# thesolderstation_v0_1.net
KiCad netlist of a schematic drawn in EAGLE
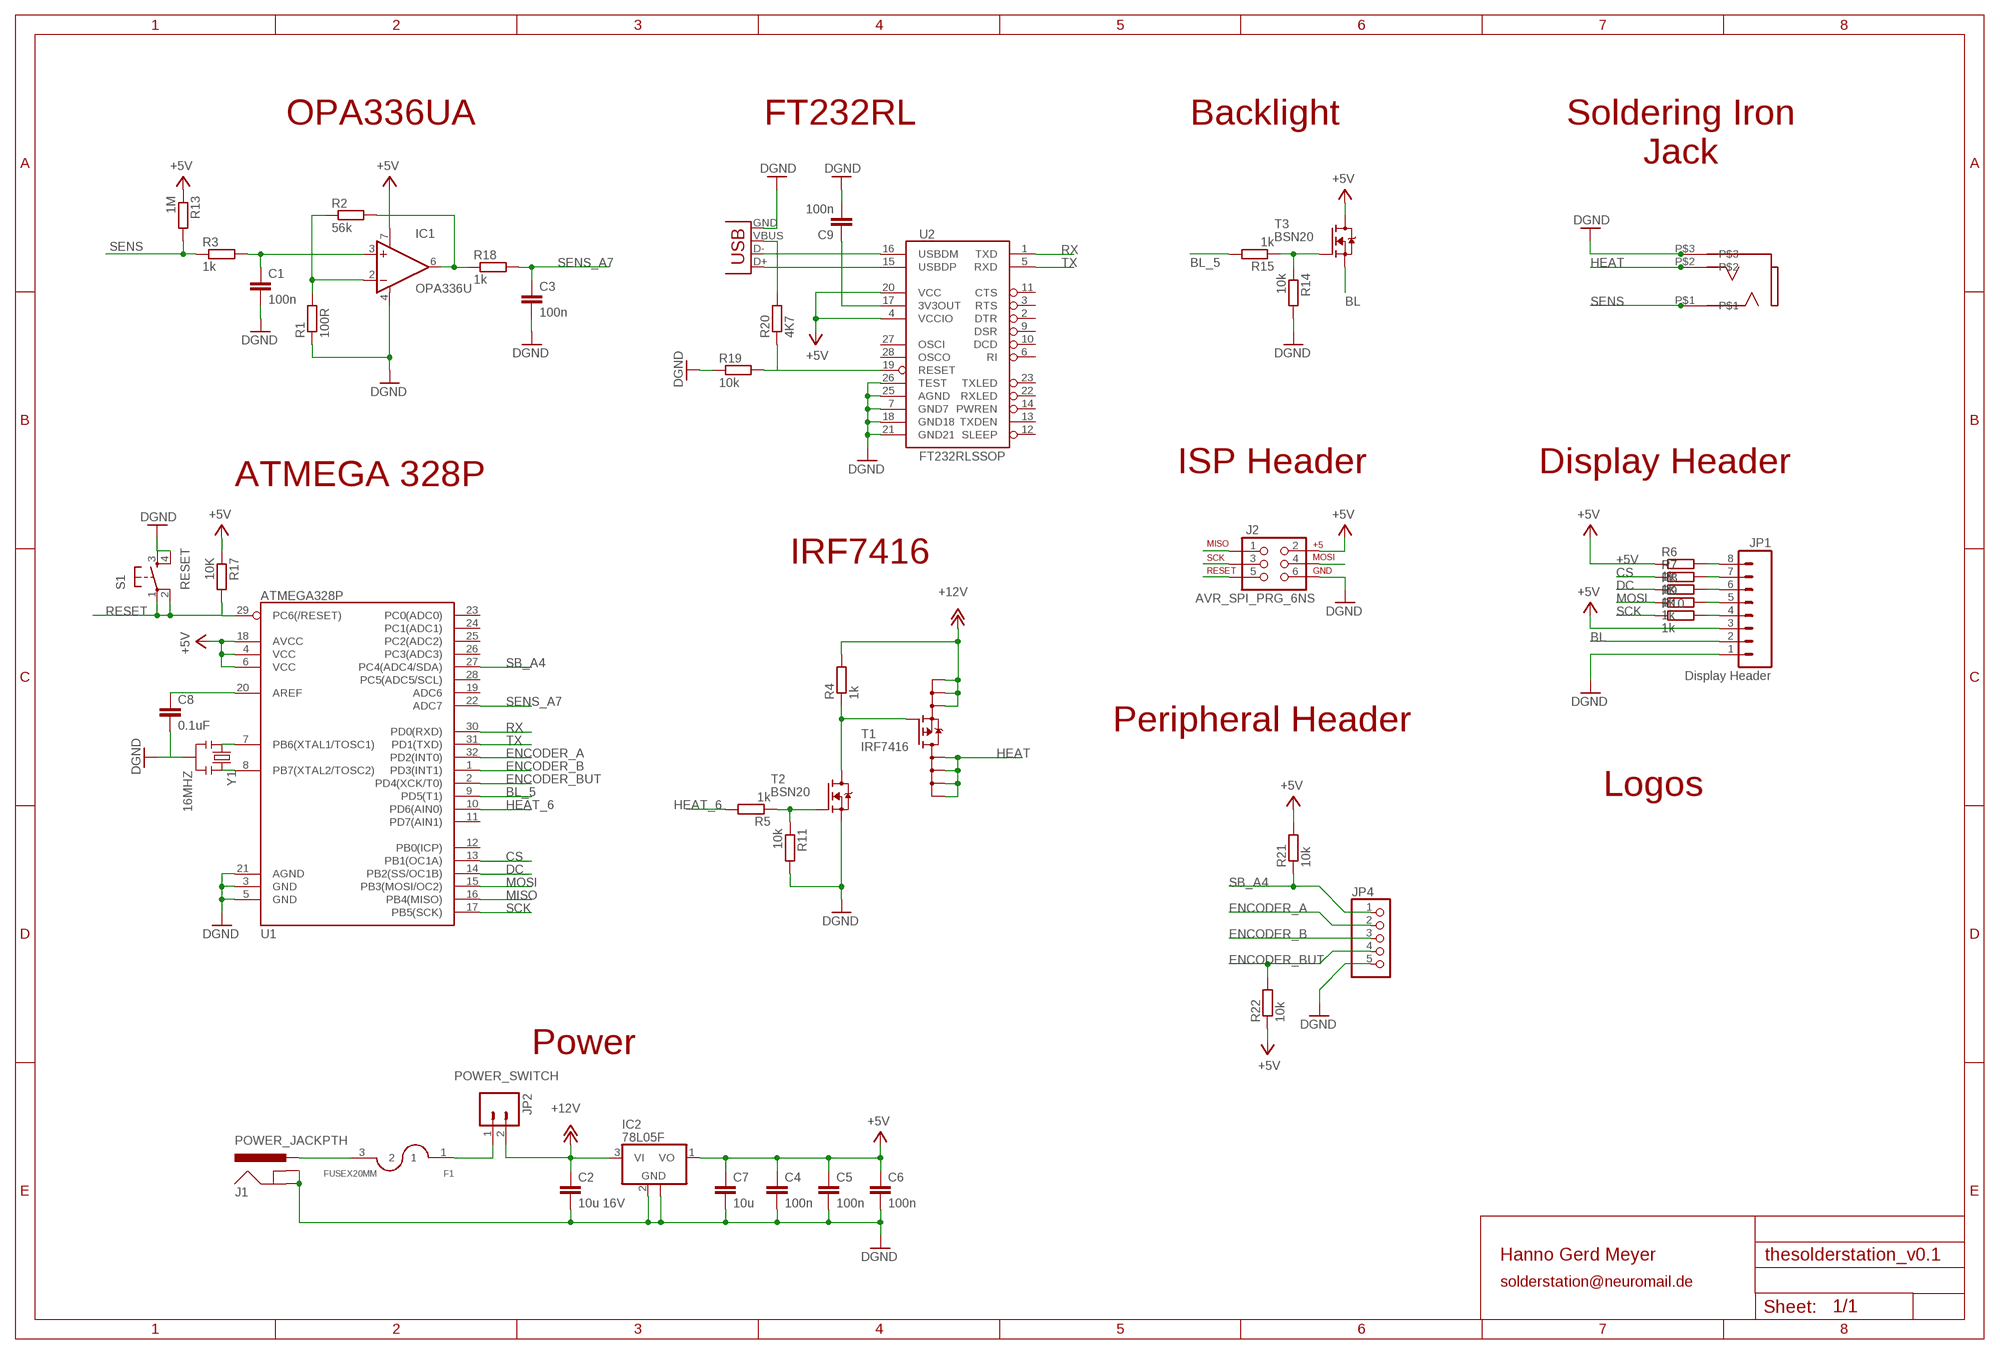
[diagram p0: schematic, sheet 1]

(export (version "E")
  (design (tool "Eeschema 10.0.6"))
  (components
    (comp (ref "C1")
      (value "100n")
      (footprint "eagle-import:C0603")
      (libsource (lib "eagle-import") (part "C-EUC0603"))
    )
    (comp (ref "C2")
      (value "10u 16V")
      (footprint "eagle-import:C1206")
      (libsource (lib "eagle-import") (part "C-EUC1206"))
    )
    (comp (ref "C3")
      (value "100n")
      (footprint "eagle-import:C0603")
      (libsource (lib "eagle-import") (part "C-EUC0603"))
    )
    (comp (ref "C4")
      (value "100n")
      (footprint "eagle-import:C0603")
      (libsource (lib "eagle-import") (part "C-EUC0603"))
    )
    (comp (ref "C5")
      (value "100n")
      (footprint "eagle-import:C0603")
      (libsource (lib "eagle-import") (part "C-EUC0603"))
    )
    (comp (ref "C6")
      (value "100n")
      (footprint "eagle-import:C0603")
      (libsource (lib "eagle-import") (part "C-EUC0603"))
    )
    (comp (ref "C7")
      (value "10u")
      (footprint "eagle-import:C1206")
      (libsource (lib "eagle-import") (part "C-EUC1206"))
    )
    (comp (ref "C8")
      (value "0.1uF")
      (footprint "eagle-import:C0603")
      (libsource (lib "eagle-import") (part "C-EUC0603"))
    )
    (comp (ref "C9")
      (value "100n")
      (footprint "eagle-import:C0603")
      (libsource (lib "eagle-import") (part "C-EUC0603"))
    )
    (comp (ref "F1")
      (value "FUSEX20MM")
      (footprint "eagle-import:FUSE_5MM")
      (libsource (lib "eagle-import") (part "FUSEX20MM"))
    )
    (comp (ref "IC1")
      (value "OPA336U")
      (footprint "eagle-import:SO08")
      (fields (field (name "MF") "TEXAS INSTRUMENT CONNECTORS") (field (name "MPN") "OPA336UA"))
      (libsource (lib "eagle-import") (part "OPA336U"))
    )
    (comp (ref "IC2")
      (value "78L05F")
      (footprint "eagle-import:SOT89")
      (libsource (lib "eagle-import") (part "78LF05"))
    )
    (comp (ref "J1")
      (value "POWER_JACKPTH")
      (footprint "eagle-import:POWER_JACK_PTH")
      (libsource (lib "eagle-import") (part "POWER_JACKPTH"))
    )
    (comp (ref "J2")
      (value "AVR_SPI_PRG_6NS")
      (footprint "eagle-import:2X3-NS")
      (libsource (lib "eagle-import") (part "AVR_SPI_PRG_6NS"))
    )
    (comp (ref "JP1")
      (value "Display Header")
      (footprint "eagle-import:1X08_LOCK")
      (libsource (lib "eagle-import") (part "M08LOCK"))
    )
    (comp (ref "JP2")
      (value "POWER_SWITCH")
      (footprint "eagle-import:1X02_LOCK_LONGPADS")
      (libsource (lib "eagle-import") (part "M02LOCK_LONGPADS"))
    )
    (comp (ref "JP4")
      (value "PINHD-1X5")
      (footprint "eagle-import:1X05")
      (libsource (lib "eagle-import") (part "PINHD-1X5"))
    )
    (comp (ref "JP5")
      (value "USB-B")
      (footprint "eagle-import:USB-B-PTH")
      (libsource (lib "eagle-import") (part "USBPTH"))
    )
    (comp (ref "R1")
      (value "100R")
      (footprint "eagle-import:R0603")
      (libsource (lib "eagle-import") (part "R-EU_R0603"))
    )
    (comp (ref "R2")
      (value "56k")
      (footprint "eagle-import:R0603")
      (libsource (lib "eagle-import") (part "R-EU_R0603"))
    )
    (comp (ref "R3")
      (value "1k")
      (footprint "eagle-import:R0603")
      (libsource (lib "eagle-import") (part "R-EU_R0603"))
    )
    (comp (ref "R4")
      (value "1k")
      (footprint "eagle-import:R0603")
      (libsource (lib "eagle-import") (part "R-EU_R0603"))
    )
    (comp (ref "R5")
      (value "1k")
      (footprint "eagle-import:R0603")
      (libsource (lib "eagle-import") (part "R-EU_R0603"))
    )
    (comp (ref "R6")
      (value "1k")
      (footprint "eagle-import:R0603")
      (libsource (lib "eagle-import") (part "R-EU_R0603"))
    )
    (comp (ref "R7")
      (value "1k")
      (footprint "eagle-import:R0603")
      (libsource (lib "eagle-import") (part "R-EU_R0603"))
    )
    (comp (ref "R8")
      (value "1k")
      (footprint "eagle-import:R0603")
      (libsource (lib "eagle-import") (part "R-EU_R0603"))
    )
    (comp (ref "R9")
      (value "1k")
      (footprint "eagle-import:R0603")
      (libsource (lib "eagle-import") (part "R-EU_R0603"))
    )
    (comp (ref "R10")
      (value "1k")
      (footprint "eagle-import:R0603")
      (libsource (lib "eagle-import") (part "R-EU_R0603"))
    )
    (comp (ref "R11")
      (value "10k")
      (footprint "eagle-import:R0603")
      (libsource (lib "eagle-import") (part "R-EU_R0603"))
    )
    (comp (ref "R13")
      (value "1M")
      (footprint "eagle-import:R0603")
      (libsource (lib "eagle-import") (part "R-EU_R0603"))
    )
    (comp (ref "R14")
      (value "10k")
      (footprint "eagle-import:R0603")
      (libsource (lib "eagle-import") (part "R-EU_R0603"))
    )
    (comp (ref "R15")
      (value "1k")
      (footprint "eagle-import:R0603")
      (libsource (lib "eagle-import") (part "R-EU_R0603"))
    )
    (comp (ref "R17")
      (value "10K")
      (footprint "eagle-import:R0603")
      (libsource (lib "eagle-import") (part "R-EU_R0603"))
    )
    (comp (ref "R18")
      (value "1k")
      (footprint "eagle-import:R0603")
      (libsource (lib "eagle-import") (part "R-EU_R0603"))
    )
    (comp (ref "R19")
      (value "10k")
      (footprint "eagle-import:R0603")
      (libsource (lib "eagle-import") (part "R-EU_R0603"))
    )
    (comp (ref "R20")
      (value "4K7")
      (footprint "eagle-import:R0603")
      (libsource (lib "eagle-import") (part "R-EU_R0603"))
    )
    (comp (ref "R21")
      (value "10k")
      (footprint "eagle-import:R0603")
      (libsource (lib "eagle-import") (part "R-EU_R0603"))
    )
    (comp (ref "R22")
      (value "10k")
      (footprint "eagle-import:R0603")
      (libsource (lib "eagle-import") (part "R-EU_R0603"))
    )
    (comp (ref "S1")
      (value "RESET")
      (footprint "eagle-import:TACTILE-PTH")
      (libsource (lib "eagle-import") (part "TAC_SWITCHPTH"))
    )
    (comp (ref "T1")
      (value "IRF7416")
      (footprint "eagle-import:SO8")
      (libsource (lib "eagle-import") (part "IRF7416"))
    )
    (comp (ref "T2")
      (value "BSN20")
      (footprint "eagle-import:SOT23")
      (libsource (lib "eagle-import") (part "BSN20"))
    )
    (comp (ref "T3")
      (value "BSN20")
      (footprint "eagle-import:SOT23")
      (libsource (lib "eagle-import") (part "BSN20"))
    )
    (comp (ref "U$1")
      (value "35RASMT2BHNTRX")
      (footprint "eagle-import:35RASMT2BHNTRX")
      (libsource (lib "eagle-import") (part "35RASMT2BHNTRX"))
    )
    (comp (ref "U1")
      (value "ATMEGA328P")
      (footprint "eagle-import:TQFP32-08")
      (libsource (lib "eagle-import") (part "ATMEGA328_SMT"))
    )
    (comp (ref "U2")
      (value "FT232RLSSOP")
      (footprint "eagle-import:SSOP28DB")
      (libsource (lib "eagle-import") (part "FT232RLSSOP"))
    )
    (comp (ref "Y1")
      (value "16MHZ")
      (footprint "eagle-import:RESONATOR-SMD")
      (libsource (lib "eagle-import") (part "RESONATOR16MHZ"))
    )
  )
  (nets
    (net (code "1") (name "+5V") (class "Default")
      (node (ref "C4") (pin "1") (pinfunction "1_1") (pintype "passive"))
      (node (ref "C5") (pin "1") (pinfunction "1_1") (pintype "passive"))
      (node (ref "C6") (pin "1") (pinfunction "1_1") (pintype "passive"))
      (node (ref "C7") (pin "1") (pinfunction "1_1") (pintype "passive"))
      (node (ref "IC1") (pin "7") (pinfunction "V+_7") (pintype "power_in"))
      (node (ref "IC2") (pin "1") (pinfunction "VO_1") (pintype "passive"))
      (node (ref "J2") (pin "2") (pinfunction "2_2") (pintype "passive"))
      (node (ref "JP1") (pin "3") (pinfunction "3_3") (pintype "passive"))
      (node (ref "R13") (pin "1") (pinfunction "1_1") (pintype "passive"))
      (node (ref "R17") (pin "1") (pinfunction "1_1") (pintype "passive"))
      (node (ref "R21") (pin "2") (pinfunction "2_2") (pintype "passive"))
      (node (ref "R22") (pin "1") (pinfunction "1_1") (pintype "passive"))
      (node (ref "R6") (pin "1") (pinfunction "1_1") (pintype "passive"))
      (node (ref "T3") (pin "3") (pinfunction "D_3") (pintype "passive"))
      (node (ref "U1") (pin "18") (pinfunction "AVCC_18") (pintype "bidirectional"))
      (node (ref "U1") (pin "4") (pinfunction "VCC_4") (pintype "bidirectional"))
      (node (ref "U1") (pin "6") (pinfunction "VCC_6") (pintype "bidirectional"))
      (node (ref "U2") (pin "20") (pinfunction "VCC_20") (pintype "power_in"))
      (node (ref "U2") (pin "4") (pinfunction "VCCIO_4") (pintype "power_in"))
    )
    (net (code "2") (name "+12V") (class "Default")
      (node (ref "C2") (pin "1") (pinfunction "1_1") (pintype "passive"))
      (node (ref "IC2") (pin "3") (pinfunction "VI_3") (pintype "input"))
      (node (ref "JP2") (pin "2") (pinfunction "2_2") (pintype "passive"))
      (node (ref "R4") (pin "2") (pinfunction "2_2") (pintype "passive"))
      (node (ref "T1") (pin "1") (pinfunction "S0_1") (pintype "passive"))
      (node (ref "T1") (pin "2") (pinfunction "S1_2") (pintype "passive"))
      (node (ref "T1") (pin "3") (pinfunction "S2_3") (pintype "passive"))
    )
    (net (code "3") (name "/BL") (class "Default")
      (node (ref "JP1") (pin "2") (pinfunction "2_2") (pintype "passive"))
      (node (ref "T3") (pin "2") (pinfunction "S_2") (pintype "passive"))
    )
    (net (code "4") (name "/BL_5") (class "Default")
      (node (ref "R15") (pin "2") (pinfunction "2_2") (pintype "passive"))
      (node (ref "U1") (pin "9") (pinfunction "PD5(T1)_9") (pintype "bidirectional"))
    )
    (net (code "5") (name "/CS") (class "Default")
      (node (ref "R7") (pin "1") (pinfunction "1_1") (pintype "passive"))
      (node (ref "U1") (pin "13") (pinfunction "PB1(OC1A)_13") (pintype "bidirectional"))
    )
    (net (code "6") (name "/DC") (class "Default")
      (node (ref "R8") (pin "1") (pinfunction "1_1") (pintype "passive"))
      (node (ref "U1") (pin "14") (pinfunction "PB2(SS/OC1B)_14") (pintype "bidirectional"))
    )
    (net (code "7") (name "/ENCODER_A") (class "Default")
      (node (ref "JP4") (pin "2") (pinfunction "2_2") (pintype "passive"))
      (node (ref "U1") (pin "32") (pinfunction "PD2(INT0)_32") (pintype "bidirectional"))
    )
    (net (code "8") (name "/ENCODER_B") (class "Default")
      (node (ref "JP4") (pin "3") (pinfunction "3_3") (pintype "passive"))
      (node (ref "U1") (pin "1") (pinfunction "PD3(INT1)_1") (pintype "bidirectional"))
    )
    (net (code "9") (name "/ENCODER_BUT") (class "Default")
      (node (ref "JP4") (pin "4") (pinfunction "4_4") (pintype "passive"))
      (node (ref "R22") (pin "2") (pinfunction "2_2") (pintype "passive"))
      (node (ref "U1") (pin "2") (pinfunction "PD4(XCK/T0)_2") (pintype "bidirectional"))
    )
    (net (code "10") (name "/HEAT") (class "Default")
      (node (ref "T1") (pin "5") (pinfunction "D0_5") (pintype "passive"))
      (node (ref "T1") (pin "6") (pinfunction "D1_6") (pintype "passive"))
      (node (ref "T1") (pin "7") (pinfunction "D2_7") (pintype "passive"))
      (node (ref "T1") (pin "8") (pinfunction "D3_8") (pintype "passive"))
      (node (ref "U$1") (pin "P$2") (pinfunction "P$2_P$2") (pintype "bidirectional"))
    )
    (net (code "11") (name "/HEAT_6") (class "Default")
      (node (ref "R5") (pin "2") (pinfunction "2_2") (pintype "passive"))
      (node (ref "U1") (pin "10") (pinfunction "PD6(AIN0)_10") (pintype "bidirectional"))
    )
    (net (code "12") (name "/MISO") (class "Default")
      (node (ref "J2") (pin "1") (pinfunction "1_1") (pintype "passive"))
      (node (ref "U1") (pin "16") (pinfunction "PB4(MISO)_16") (pintype "bidirectional"))
    )
    (net (code "13") (name "/MOSI") (class "Default")
      (node (ref "J2") (pin "4") (pinfunction "4_4") (pintype "passive"))
      (node (ref "R9") (pin "1") (pinfunction "1_1") (pintype "passive"))
      (node (ref "U1") (pin "15") (pinfunction "PB3(MOSI/OC2)_15") (pintype "bidirectional"))
    )
    (net (code "14") (name "/RESET") (class "Default")
      (node (ref "J2") (pin "5") (pinfunction "5_5") (pintype "passive"))
      (node (ref "R17") (pin "2") (pinfunction "2_2") (pintype "passive"))
      (node (ref "S1") (pin "1") (pinfunction "1_1") (pintype "passive"))
      (node (ref "S1") (pin "2") (pinfunction "2_2") (pintype "passive"))
      (node (ref "U1") (pin "29") (pinfunction "PC6(/RESET)_29") (pintype "bidirectional"))
    )
    (net (code "15") (name "/RX") (class "Default")
      (node (ref "U1") (pin "30") (pinfunction "PD0(RXD)_30") (pintype "bidirectional"))
      (node (ref "U2") (pin "1") (pinfunction "TXD_1") (pintype "output"))
    )
    (net (code "16") (name "/SB_A4") (class "Default")
      (node (ref "JP4") (pin "1") (pinfunction "1_1") (pintype "passive"))
      (node (ref "R21") (pin "1") (pinfunction "1_1") (pintype "passive"))
      (node (ref "U1") (pin "27") (pinfunction "PC4(ADC4/SDA)_27") (pintype "bidirectional"))
    )
    (net (code "17") (name "/SCK") (class "Default")
      (node (ref "J2") (pin "3") (pinfunction "3_3") (pintype "passive"))
      (node (ref "R10") (pin "1") (pinfunction "1_1") (pintype "passive"))
      (node (ref "U1") (pin "17") (pinfunction "PB5(SCK)_17") (pintype "bidirectional"))
    )
    (net (code "18") (name "/SENS") (class "Default")
      (node (ref "R13") (pin "2") (pinfunction "2_2") (pintype "passive"))
      (node (ref "R3") (pin "1") (pinfunction "1_1") (pintype "passive"))
      (node (ref "U$1") (pin "P$1") (pinfunction "P$1_P$1") (pintype "bidirectional"))
    )
    (net (code "19") (name "/SENS_A7") (class "Default")
      (node (ref "C3") (pin "1") (pinfunction "1_1") (pintype "passive"))
      (node (ref "R18") (pin "2") (pinfunction "2_2") (pintype "passive"))
      (node (ref "U1") (pin "22") (pinfunction "ADC7_22") (pintype "bidirectional"))
    )
    (net (code "20") (name "/TX") (class "Default")
      (node (ref "U1") (pin "31") (pinfunction "PD1(TXD)_31") (pintype "bidirectional"))
      (node (ref "U2") (pin "5") (pinfunction "RXD_5") (pintype "input"))
    )
    (net (code "21") (name "DGND") (class "Default")
      (node (ref "C1") (pin "2") (pinfunction "2_2") (pintype "passive"))
      (node (ref "C2") (pin "2") (pinfunction "2_2") (pintype "passive"))
      (node (ref "C3") (pin "2") (pinfunction "2_2") (pintype "passive"))
      (node (ref "C4") (pin "2") (pinfunction "2_2") (pintype "passive"))
      (node (ref "C5") (pin "2") (pinfunction "2_2") (pintype "passive"))
      (node (ref "C6") (pin "2") (pinfunction "2_2") (pintype "passive"))
      (node (ref "C7") (pin "2") (pinfunction "2_2") (pintype "passive"))
      (node (ref "C8") (pin "2") (pinfunction "2_2") (pintype "passive"))
      (node (ref "C9") (pin "2") (pinfunction "2_2") (pintype "passive"))
      (node (ref "IC1") (pin "4") (pinfunction "V-_4") (pintype "power_in"))
      (node (ref "IC2") (pin "2") (pinfunction "GND_2") (pintype "passive"))
      (node (ref "IC2") (pin "2@1") (pinfunction "GND_2@1") (pintype "passive"))
      (node (ref "J1") (pin "GND") (pinfunction "GND_GND") (pintype "bidirectional"))
      (node (ref "J1") (pin "GNDBREAK") (pinfunction "GNDBREAK_GNDBREAK") (pintype "bidirectional"))
      (node (ref "J2") (pin "6") (pinfunction "6_6") (pintype "passive"))
      (node (ref "JP1") (pin "1") (pinfunction "1_1") (pintype "passive"))
      (node (ref "JP4") (pin "5") (pinfunction "5_5") (pintype "passive"))
      (node (ref "JP5") (pin "GND") (pinfunction "GND_GND") (pintype "bidirectional"))
      (node (ref "R1") (pin "1") (pinfunction "1_1") (pintype "passive"))
      (node (ref "R11") (pin "2") (pinfunction "2_2") (pintype "passive"))
      (node (ref "R14") (pin "2") (pinfunction "2_2") (pintype "passive"))
      (node (ref "R19") (pin "1") (pinfunction "1_1") (pintype "passive"))
      (node (ref "S1") (pin "3") (pinfunction "3_3") (pintype "passive"))
      (node (ref "S1") (pin "4") (pinfunction "4_4") (pintype "passive"))
      (node (ref "T2") (pin "2") (pinfunction "S_2") (pintype "passive"))
      (node (ref "U$1") (pin "P$3") (pinfunction "P$3_P$3") (pintype "bidirectional"))
      (node (ref "U1") (pin "21") (pinfunction "AGND_21") (pintype "bidirectional"))
      (node (ref "U1") (pin "3") (pinfunction "GND_3") (pintype "bidirectional"))
      (node (ref "U1") (pin "5") (pinfunction "GND_5") (pintype "bidirectional"))
      (node (ref "U2") (pin "18") (pinfunction "GND18_18") (pintype "power_in"))
      (node (ref "U2") (pin "21") (pinfunction "GND21_21") (pintype "power_in"))
      (node (ref "U2") (pin "25") (pinfunction "AGND_25") (pintype "power_in"))
      (node (ref "U2") (pin "26") (pinfunction "TEST_26") (pintype "input"))
      (node (ref "U2") (pin "7") (pinfunction "GND7_7") (pintype "power_in"))
      (node (ref "Y1") (pin "2") (pinfunction "2_2") (pintype "passive"))
    )
    (net (code "22") (name "Net-(F1-2)") (class "Default")
      (node (ref "F1") (pin "3") (pinfunction "2_3") (pintype "bidirectional"))
      (node (ref "J1") (pin "PWR") (pinfunction "PWR_PWR") (pintype "bidirectional"))
    )
    (net (code "23") (name "Net-(F1-Pad1)") (class "Default")
      (node (ref "F1") (pin "1") (pinfunction "1_1") (pintype "bidirectional"))
      (node (ref "JP2") (pin "1") (pinfunction "1_1") (pintype "passive"))
    )
    (net (code "24") (name "Net-(IC1-+IN)") (class "Default")
      (node (ref "C1") (pin "1") (pinfunction "1_1") (pintype "passive"))
      (node (ref "IC1") (pin "3") (pinfunction "+IN_3") (pintype "input"))
      (node (ref "R3") (pin "2") (pinfunction "2_2") (pintype "passive"))
    )
    (net (code "25") (name "Net-(IC1--IN)") (class "Default")
      (node (ref "IC1") (pin "2") (pinfunction "-IN_2") (pintype "input"))
      (node (ref "R1") (pin "2") (pinfunction "2_2") (pintype "passive"))
      (node (ref "R2") (pin "1") (pinfunction "1_1") (pintype "passive"))
    )
    (net (code "26") (name "Net-(IC1-OUT)") (class "Default")
      (node (ref "IC1") (pin "6") (pinfunction "OUT_6") (pintype "output"))
      (node (ref "R18") (pin "1") (pinfunction "1_1") (pintype "passive"))
      (node (ref "R2") (pin "2") (pinfunction "2_2") (pintype "passive"))
    )
    (net (code "27") (name "Net-(JP1-Pad4)") (class "Default")
      (node (ref "JP1") (pin "4") (pinfunction "4_4") (pintype "passive"))
      (node (ref "R10") (pin "2") (pinfunction "2_2") (pintype "passive"))
    )
    (net (code "28") (name "Net-(JP1-Pad5)") (class "Default")
      (node (ref "JP1") (pin "5") (pinfunction "5_5") (pintype "passive"))
      (node (ref "R9") (pin "2") (pinfunction "2_2") (pintype "passive"))
    )
    (net (code "29") (name "Net-(JP1-Pad6)") (class "Default")
      (node (ref "JP1") (pin "6") (pinfunction "6_6") (pintype "passive"))
      (node (ref "R8") (pin "2") (pinfunction "2_2") (pintype "passive"))
    )
    (net (code "30") (name "Net-(JP1-Pad7)") (class "Default")
      (node (ref "JP1") (pin "7") (pinfunction "7_7") (pintype "passive"))
      (node (ref "R7") (pin "2") (pinfunction "2_2") (pintype "passive"))
    )
    (net (code "31") (name "Net-(JP1-Pad8)") (class "Default")
      (node (ref "JP1") (pin "8") (pinfunction "8_8") (pintype "passive"))
      (node (ref "R6") (pin "2") (pinfunction "2_2") (pintype "passive"))
    )
    (net (code "32") (name "Net-(JP5-PadVBUS)") (class "Default")
      (node (ref "JP5") (pin "VBUS") (pinfunction "VBUS_VBUS") (pintype "bidirectional"))
      (node (ref "R20") (pin "2") (pinfunction "2_2") (pintype "passive"))
    )
    (net (code "33") (name "Net-(T1-G)") (class "Default")
      (node (ref "R4") (pin "1") (pinfunction "1_1") (pintype "passive"))
      (node (ref "T1") (pin "4") (pinfunction "G_4") (pintype "passive"))
      (node (ref "T2") (pin "3") (pinfunction "D_3") (pintype "passive"))
    )
    (net (code "34") (name "Net-(T2-G)") (class "Default")
      (node (ref "R11") (pin "1") (pinfunction "1_1") (pintype "passive"))
      (node (ref "R5") (pin "1") (pinfunction "1_1") (pintype "passive"))
      (node (ref "T2") (pin "1") (pinfunction "G_1") (pintype "passive"))
    )
    (net (code "35") (name "Net-(T3-G)") (class "Default")
      (node (ref "R14") (pin "1") (pinfunction "1_1") (pintype "passive"))
      (node (ref "R15") (pin "1") (pinfunction "1_1") (pintype "passive"))
      (node (ref "T3") (pin "1") (pinfunction "G_1") (pintype "passive"))
    )
    (net (code "36") (name "Net-(U1-AREF)") (class "Default")
      (node (ref "C8") (pin "1") (pinfunction "1_1") (pintype "passive"))
      (node (ref "U1") (pin "20") (pinfunction "AREF_20") (pintype "bidirectional"))
    )
    (net (code "37") (name "Net-(U1-PB6(XTAL1{slash}TOSC1))") (class "Default")
      (node (ref "U1") (pin "7") (pinfunction "PB6(XTAL1/TOSC1)_7") (pintype "bidirectional"))
      (node (ref "Y1") (pin "1") (pinfunction "1_1") (pintype "passive"))
    )
    (net (code "38") (name "Net-(U1-PB7(XTAL2{slash}TOSC2))") (class "Default")
      (node (ref "U1") (pin "8") (pinfunction "PB7(XTAL2/TOSC2)_8") (pintype "bidirectional"))
      (node (ref "Y1") (pin "3") (pinfunction "3_3") (pintype "passive"))
    )
    (net (code "39") (name "Net-(U2-3V3OUT)") (class "Default")
      (node (ref "C9") (pin "1") (pinfunction "1_1") (pintype "passive"))
      (node (ref "U2") (pin "17") (pinfunction "3V3OUT_17") (pintype "output"))
    )
    (net (code "40") (name "Net-(U2-RESET)") (class "Default")
      (node (ref "R19") (pin "2") (pinfunction "2_2") (pintype "passive"))
      (node (ref "R20") (pin "1") (pinfunction "1_1") (pintype "passive"))
      (node (ref "U2") (pin "19") (pinfunction "RESET_19") (pintype "input"))
    )
    (net (code "41") (name "Net-(U2-USBDM)") (class "Default")
      (node (ref "JP5") (pin "D-") (pinfunction "D-_D-") (pintype "bidirectional"))
      (node (ref "U2") (pin "16") (pinfunction "USBDM_16") (pintype "bidirectional"))
    )
    (net (code "42") (name "Net-(U2-USBDP)") (class "Default")
      (node (ref "JP5") (pin "D+") (pinfunction "D+_D+") (pintype "bidirectional"))
      (node (ref "U2") (pin "15") (pinfunction "USBDP_15") (pintype "bidirectional"))
    )
    (net (code "43") (name "unconnected-(U1-ADC6-Pad19)") (class "Default")
      (node (ref "U1") (pin "19") (pinfunction "ADC6_19") (pintype "bidirectional"))
    )
    (net (code "44") (name "unconnected-(U1-PB0(ICP)-Pad12)") (class "Default")
      (node (ref "U1") (pin "12") (pinfunction "PB0(ICP)_12") (pintype "bidirectional"))
    )
    (net (code "45") (name "unconnected-(U1-PC0(ADC0)-Pad23)") (class "Default")
      (node (ref "U1") (pin "23") (pinfunction "PC0(ADC0)_23") (pintype "bidirectional"))
    )
    (net (code "46") (name "unconnected-(U1-PC1(ADC1)-Pad24)") (class "Default")
      (node (ref "U1") (pin "24") (pinfunction "PC1(ADC1)_24") (pintype "bidirectional"))
    )
    (net (code "47") (name "unconnected-(U1-PC2(ADC2)-Pad25)") (class "Default")
      (node (ref "U1") (pin "25") (pinfunction "PC2(ADC2)_25") (pintype "bidirectional"))
    )
    (net (code "48") (name "unconnected-(U1-PC3(ADC3)-Pad26)") (class "Default")
      (node (ref "U1") (pin "26") (pinfunction "PC3(ADC3)_26") (pintype "bidirectional"))
    )
    (net (code "49") (name "unconnected-(U1-PC5(ADC5{slash}SCL)-Pad28)") (class "Default")
      (node (ref "U1") (pin "28") (pinfunction "PC5(ADC5/SCL)_28") (pintype "bidirectional"))
    )
    (net (code "50") (name "unconnected-(U1-PD7(AIN1)-Pad11)") (class "Default")
      (node (ref "U1") (pin "11") (pinfunction "PD7(AIN1)_11") (pintype "bidirectional"))
    )
    (net (code "51") (name "unconnected-(U2-CTS-Pad11)") (class "Default")
      (node (ref "U2") (pin "11") (pinfunction "CTS_11") (pintype "input"))
    )
    (net (code "52") (name "unconnected-(U2-DCD-Pad10)") (class "Default")
      (node (ref "U2") (pin "10") (pinfunction "DCD_10") (pintype "input"))
    )
    (net (code "53") (name "unconnected-(U2-DSR-Pad9)") (class "Default")
      (node (ref "U2") (pin "9") (pinfunction "DSR_9") (pintype "input"))
    )
    (net (code "54") (name "unconnected-(U2-DTR-Pad2)") (class "Default")
      (node (ref "U2") (pin "2") (pinfunction "DTR_2") (pintype "output"))
    )
    (net (code "55") (name "unconnected-(U2-OSCI-Pad27)") (class "Default")
      (node (ref "U2") (pin "27") (pinfunction "OSCI_27") (pintype "input"))
    )
    (net (code "56") (name "unconnected-(U2-OSCO-Pad28)") (class "Default")
      (node (ref "U2") (pin "28") (pinfunction "OSCO_28") (pintype "output"))
    )
    (net (code "57") (name "unconnected-(U2-PWREN-Pad14)") (class "Default")
      (node (ref "U2") (pin "14") (pinfunction "PWREN_14") (pintype "input"))
    )
    (net (code "58") (name "unconnected-(U2-RI-Pad6)") (class "Default")
      (node (ref "U2") (pin "6") (pinfunction "RI_6") (pintype "input"))
    )
    (net (code "59") (name "unconnected-(U2-RTS-Pad3)") (class "Default")
      (node (ref "U2") (pin "3") (pinfunction "RTS_3") (pintype "output"))
    )
    (net (code "60") (name "unconnected-(U2-RXLED-Pad22)") (class "Default")
      (node (ref "U2") (pin "22") (pinfunction "RXLED_22") (pintype "input"))
    )
    (net (code "61") (name "unconnected-(U2-SLEEP-Pad12)") (class "Default")
      (node (ref "U2") (pin "12") (pinfunction "SLEEP_12") (pintype "input"))
    )
    (net (code "62") (name "unconnected-(U2-TXDEN-Pad13)") (class "Default")
      (node (ref "U2") (pin "13") (pinfunction "TXDEN_13") (pintype "input"))
    )
    (net (code "63") (name "unconnected-(U2-TXLED-Pad23)") (class "Default")
      (node (ref "U2") (pin "23") (pinfunction "TXLED_23") (pintype "input"))
    )
  )
)
